# panel.net
KiCad netlist of a schematic drawn in EAGLE
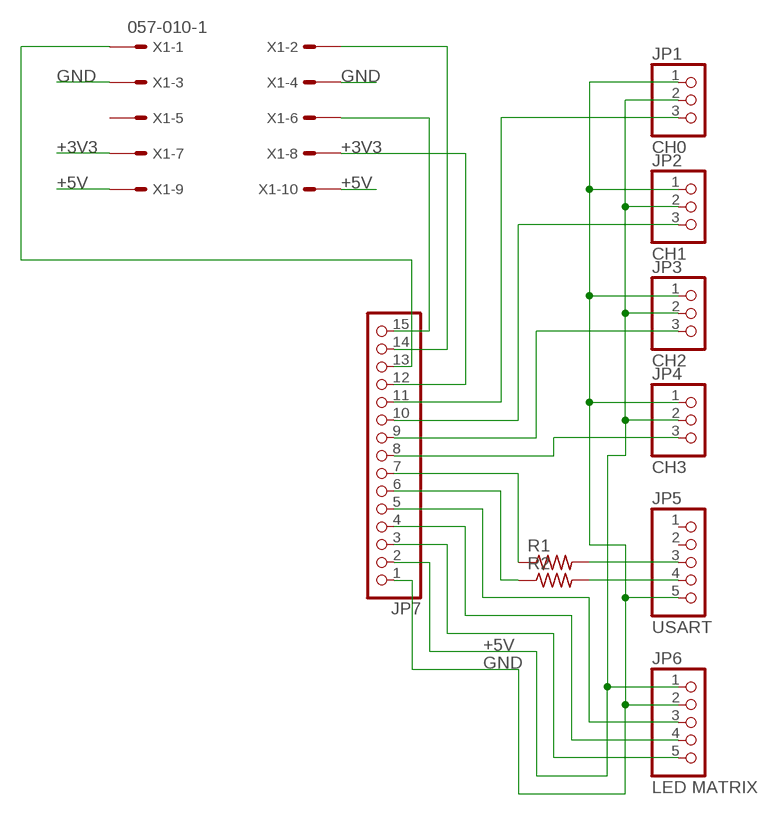
[diagram p0: schematic, sheet 1]

(export (version "E")
  (design (tool "Eeschema 10.0.6"))
  (components
    (comp (ref "JP1")
      (value "CH0")
      (footprint "eagle-import:1X03")
      (libsource (lib "eagle-import") (part "PINHD-1X3"))
    )
    (comp (ref "JP2")
      (value "CH1")
      (footprint "eagle-import:1X03")
      (libsource (lib "eagle-import") (part "PINHD-1X3"))
    )
    (comp (ref "JP3")
      (value "CH2")
      (footprint "eagle-import:1X03")
      (libsource (lib "eagle-import") (part "PINHD-1X3"))
    )
    (comp (ref "JP4")
      (value "CH3")
      (footprint "eagle-import:1X03")
      (libsource (lib "eagle-import") (part "PINHD-1X3"))
    )
    (comp (ref "JP5")
      (value "USART")
      (footprint "eagle-import:1X05")
      (libsource (lib "eagle-import") (part "PINHD-1X5"))
    )
    (comp (ref "JP6")
      (value "LED MATRIX")
      (footprint "eagle-import:1X05")
      (libsource (lib "eagle-import") (part "PINHD-1X5"))
    )
    (comp (ref "JP7")
      (value "PINHD-1X15")
      (footprint "eagle-import:1X15")
      (libsource (lib "eagle-import") (part "PINHD-1X15"))
    )
    (comp (ref "R1")
      (value "R-US_0204/7")
      (footprint "eagle-import:0204_7")
      (libsource (lib "eagle-import") (part "R-US_0204/7"))
    )
    (comp (ref "R2")
      (value "R-US_0204/7")
      (footprint "eagle-import:0204_7")
      (libsource (lib "eagle-import") (part "R-US_0204/7"))
    )
    (comp (ref "X1")
      (value "057-010-1")
      (footprint "eagle-import:057-010-1")
      (libsource (lib "eagle-import") (part "057-010-1"))
    )
  )
  (nets
    (net (code "1") (name "/+3V3") (class "Default")
      (node (ref "JP7") (pin "12") (pinfunction "12_12") (pintype "passive"))
      (node (ref "X1") (pin "7") (pinfunction "S_7") (pintype "passive"))
      (node (ref "X1") (pin "8") (pinfunction "S_8") (pintype "passive"))
    )
    (net (code "2") (name "/+5V") (class "Default")
      (node (ref "JP1") (pin "2") (pinfunction "2_2") (pintype "passive"))
      (node (ref "JP2") (pin "2") (pinfunction "2_2") (pintype "passive"))
      (node (ref "JP3") (pin "2") (pinfunction "2_2") (pintype "passive"))
      (node (ref "JP4") (pin "2") (pinfunction "2_2") (pintype "passive"))
      (node (ref "JP6") (pin "1") (pinfunction "1_1") (pintype "passive"))
      (node (ref "JP7") (pin "2") (pinfunction "2_2") (pintype "passive"))
      (node (ref "X1") (pin "10") (pinfunction "S_10") (pintype "passive"))
      (node (ref "X1") (pin "9") (pinfunction "S_9") (pintype "passive"))
    )
    (net (code "3") (name "/GND") (class "Default")
      (node (ref "JP1") (pin "1") (pinfunction "1_1") (pintype "passive"))
      (node (ref "JP2") (pin "1") (pinfunction "1_1") (pintype "passive"))
      (node (ref "JP3") (pin "1") (pinfunction "1_1") (pintype "passive"))
      (node (ref "JP4") (pin "1") (pinfunction "1_1") (pintype "passive"))
      (node (ref "JP5") (pin "5") (pinfunction "5_5") (pintype "passive"))
      (node (ref "JP6") (pin "2") (pinfunction "2_2") (pintype "passive"))
      (node (ref "JP7") (pin "1") (pinfunction "1_1") (pintype "passive"))
      (node (ref "X1") (pin "3") (pinfunction "S_3") (pintype "passive"))
      (node (ref "X1") (pin "4") (pinfunction "S_4") (pintype "passive"))
    )
    (net (code "4") (name "Net-(JP1-Pad3)") (class "Default")
      (node (ref "JP1") (pin "3") (pinfunction "3_3") (pintype "passive"))
      (node (ref "JP7") (pin "11") (pinfunction "11_11") (pintype "passive"))
    )
    (net (code "5") (name "Net-(JP2-Pad3)") (class "Default")
      (node (ref "JP2") (pin "3") (pinfunction "3_3") (pintype "passive"))
      (node (ref "JP7") (pin "10") (pinfunction "10_10") (pintype "passive"))
    )
    (net (code "6") (name "Net-(JP3-Pad3)") (class "Default")
      (node (ref "JP3") (pin "3") (pinfunction "3_3") (pintype "passive"))
      (node (ref "JP7") (pin "9") (pinfunction "9_9") (pintype "passive"))
    )
    (net (code "7") (name "Net-(JP4-Pad3)") (class "Default")
      (node (ref "JP4") (pin "3") (pinfunction "3_3") (pintype "passive"))
      (node (ref "JP7") (pin "8") (pinfunction "8_8") (pintype "passive"))
    )
    (net (code "8") (name "Net-(JP5-Pad3)") (class "Default")
      (node (ref "JP5") (pin "3") (pinfunction "3_3") (pintype "passive"))
      (node (ref "R1") (pin "2") (pinfunction "2_2") (pintype "passive"))
    )
    (net (code "9") (name "Net-(JP5-Pad4)") (class "Default")
      (node (ref "JP5") (pin "4") (pinfunction "4_4") (pintype "passive"))
      (node (ref "R2") (pin "2") (pinfunction "2_2") (pintype "passive"))
    )
    (net (code "10") (name "Net-(JP6-Pad3)") (class "Default")
      (node (ref "JP6") (pin "3") (pinfunction "3_3") (pintype "passive"))
      (node (ref "JP7") (pin "5") (pinfunction "5_5") (pintype "passive"))
    )
    (net (code "11") (name "Net-(JP6-Pad4)") (class "Default")
      (node (ref "JP6") (pin "4") (pinfunction "4_4") (pintype "passive"))
      (node (ref "JP7") (pin "4") (pinfunction "4_4") (pintype "passive"))
    )
    (net (code "12") (name "Net-(JP6-Pad5)") (class "Default")
      (node (ref "JP6") (pin "5") (pinfunction "5_5") (pintype "passive"))
      (node (ref "JP7") (pin "3") (pinfunction "3_3") (pintype "passive"))
    )
    (net (code "13") (name "Net-(JP7-Pad6)") (class "Default")
      (node (ref "JP7") (pin "6") (pinfunction "6_6") (pintype "passive"))
      (node (ref "R2") (pin "1") (pinfunction "1_1") (pintype "passive"))
    )
    (net (code "14") (name "Net-(JP7-Pad7)") (class "Default")
      (node (ref "JP7") (pin "7") (pinfunction "7_7") (pintype "passive"))
      (node (ref "R1") (pin "1") (pinfunction "1_1") (pintype "passive"))
    )
    (net (code "15") (name "Net-(X1A-S)") (class "Default")
      (node (ref "JP7") (pin "13") (pinfunction "13_13") (pintype "passive"))
      (node (ref "X1") (pin "1") (pinfunction "S_1") (pintype "passive"))
    )
    (net (code "16") (name "Net-(X1C-S)") (class "Default")
      (node (ref "JP7") (pin "14") (pinfunction "14_14") (pintype "passive"))
      (node (ref "X1") (pin "2") (pinfunction "S_2") (pintype "passive"))
    )
    (net (code "17") (name "Net-(X1G-S)") (class "Default")
      (node (ref "JP7") (pin "15") (pinfunction "15_15") (pintype "passive"))
      (node (ref "X1") (pin "6") (pinfunction "S_6") (pintype "passive"))
    )
    (net (code "18") (name "unconnected-(JP5-Pad1)") (class "Default")
      (node (ref "JP5") (pin "1") (pinfunction "1_1") (pintype "passive"))
    )
    (net (code "19") (name "unconnected-(JP5-Pad2)") (class "Default")
      (node (ref "JP5") (pin "2") (pinfunction "2_2") (pintype "passive"))
    )
    (net (code "20") (name "unconnected-(X1F-S-Pad5)") (class "Default")
      (node (ref "X1") (pin "5") (pinfunction "S_5") (pintype "passive"))
    )
  )
)
